# Relay_IO.net
KiCad netlist of a schematic drawn in Altium Designer
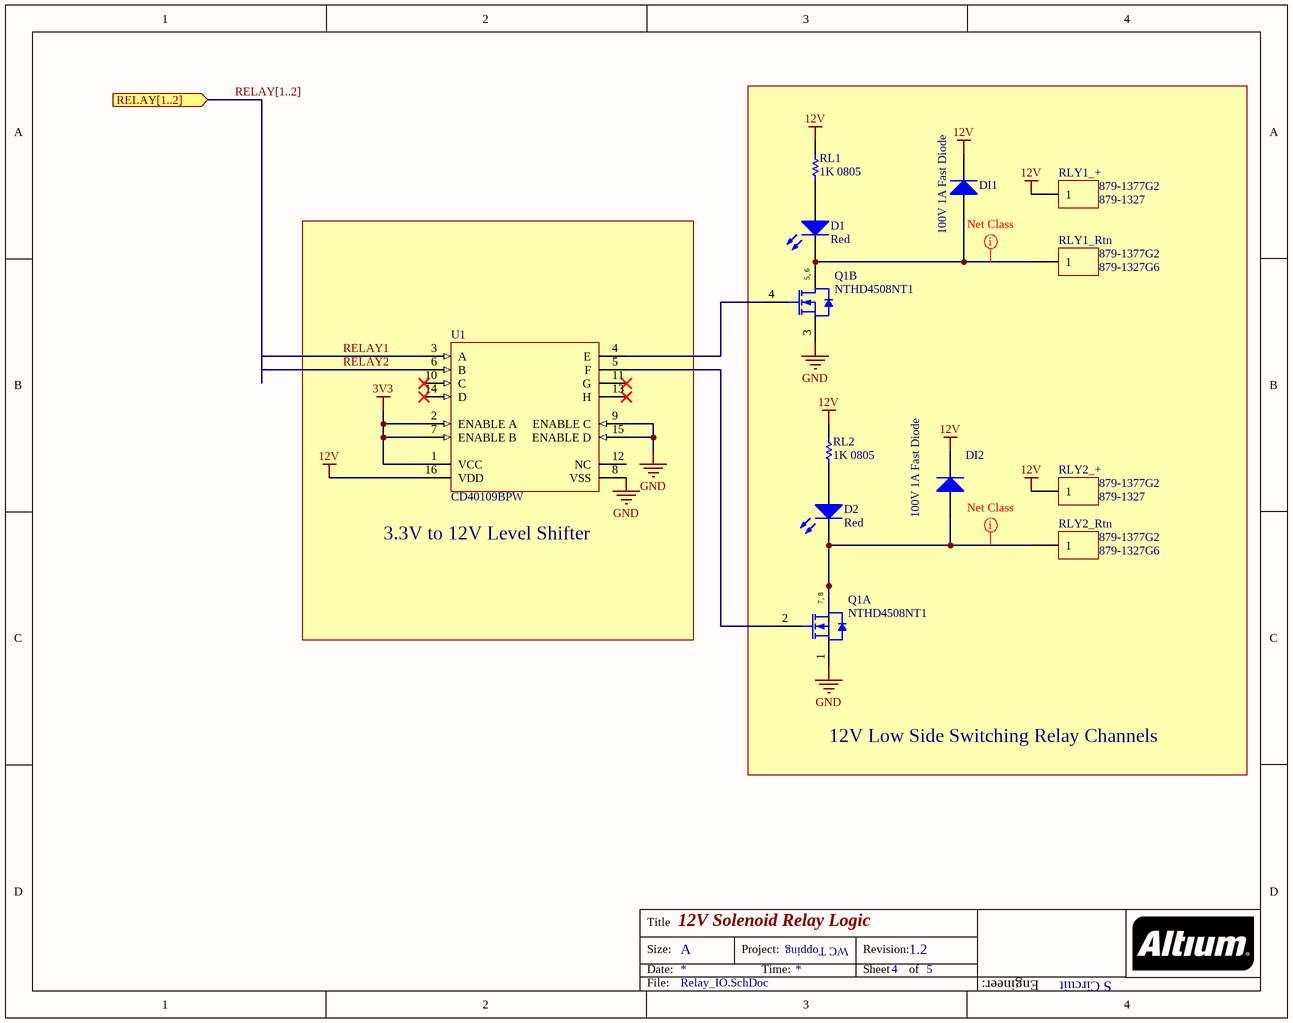
[diagram p0: Relay_IO.SchDoc]

(export (version "E")
  (design (tool "Eeschema 10.0.6"))
  (components
    (comp (ref "D1")
      (value "LED Red")
      (footprint "0603_A")
      (description "SMD mono-color Chip LED, WL-SMCW, Red")
      (fields
        (field (name "COLOR") "Red")
        (field (name "MANUFACTURER") "Wurth Electronics Inc")
        (field (name "MANUFACTURER PART NUMBER") "150060RS75000")
      )
      (libsource (lib "WCT") (part "LED_Red0603"))
    )
    (comp (ref "D2")
      (value "LED Red")
      (footprint "0603_A")
      (description "SMD mono-color Chip LED, WL-SMCW, Red")
      (fields
        (field (name "COLOR") "Red")
        (field (name "MANUFACTURER") "Wurth Electronics Inc")
        (field (name "MANUFACTURER PART NUMBER") "150060RS75000")
      )
      (libsource (lib "WCT") (part "LED_Red0603"))
    )
    (comp (ref "DI1")
      (value "100V 1A Fast Diode")
      (footprint "DO-35")
      (description "High Conductance Fast Diode")
      (fields
        (field (name "MANUFACTURER") "ON Semiconductor")
        (field (name "MANUFACTURER PART NUMBER") "MUR110RLG")
      )
      (libsource (lib "WCT") (part "Diode 1N4148"))
    )
    (comp (ref "DI2")
      (value "100V 1A Fast Diode")
      (footprint "DO-35")
      (description "High Conductance Fast Diode")
      (fields
        (field (name "MANUFACTURER") "ON Semiconductor")
        (field (name "MANUFACTURER PART NUMBER") "MUR110RLG")
      )
      (libsource (lib "WCT") (part "Diode 1N4148"))
    )
    (comp (ref "Q1")
      (value "NTHD4508NT1")
      (footprint "ONSC-CHIPFET-8-1206A-03_S2_V")
      (description "Power MOSFET, 20 V, 4.1 A, Dual N-Channel, 8-Pin CHIPFET, Tape and Reel")
      (fields
        (field (name "MANUFACTURER") "On Semiconductor")
        (field (name "MANUFACTURER PART NUMBER") "NTHD4508NT1G")
      )
      (libsource (lib "WCT") (part "NTHD4508NT1"))
    )
    (comp (ref "RL1")
      (value "1K 0805")
      (footprint "0805_L")
      (fields
        (field (name "MANUFACTURER") "Panasonic Electronic Components")
        (field (name "MANUFACTURER PART NUMBER") "ERJ-6GEYJ102V")
        (field (name "TOLERANCE") "±5%")
      )
      (libsource (lib "ICEdigikey") (part "Res1K_0805"))
    )
    (comp (ref "RL2")
      (value "1K 0805")
      (footprint "0805_L")
      (fields
        (field (name "MANUFACTURER") "Panasonic Electronic Components")
        (field (name "MANUFACTURER PART NUMBER") "ERJ-6GEYJ102V")
        (field (name "TOLERANCE") "±5%")
      )
      (libsource (lib "ICEdigikey") (part "Res1K_0805"))
    )
    (comp (ref "RLY1_+")
      (value "Anderson-1Pin RED_PCB_RHT")
      (footprint "Anderson_Red_RHT_BOT")
      (description "1 pin Anderson")
      (fields
        (field (name "MANUFACTURER") "Anderson Power Products (APP)")
        (field (name "MANUFACTURER PART NUMBER") "1377G1, 1377G2, 1327-BK,137G6-BK")
        (field (name "SUPPLIER PART NUMBER 1") "879-1377G2")
        (field (name "SUPPLIER PART NUMBER 2") "879-1327")
      )
      (libsource (lib "WCT") (part "Anderson-1Pin RED_PCB_RHT"))
    )
    (comp (ref "RLY1_Rtn")
      (value "Anderson-1Pin BLK_PCB_RHT")
      (footprint "Anderson_BLK_RHT_BOT")
      (description "1 pin Anderson")
      (fields
        (field (name "MANUFACTURER") "Anderson Power Products (APP)")
        (field (name "MANUFACTURER PART NUMBER") "1377G1, 1377G2, 1327-BK,137G6-BK")
        (field (name "SUPPLIER PART NUMBER 1") "879-1377G2")
        (field (name "SUPPLIER PART NUMBER 2") "879-1327G6")
      )
      (libsource (lib "WCT") (part "Anderson-1Pin BLK_PCB_RHT"))
    )
    (comp (ref "RLY2_+")
      (value "Anderson-1Pin RED_PCB_RHT")
      (footprint "Anderson_Red_RHT_BOT")
      (description "1 pin Anderson")
      (fields
        (field (name "MANUFACTURER") "Anderson Power Products (APP)")
        (field (name "MANUFACTURER PART NUMBER") "1377G1, 1377G2, 1327-BK,137G6-BK")
        (field (name "SUPPLIER PART NUMBER 1") "879-1377G2")
        (field (name "SUPPLIER PART NUMBER 2") "879-1327")
      )
      (libsource (lib "WCT") (part "Anderson-1Pin RED_PCB_RHT"))
    )
    (comp (ref "RLY2_Rtn")
      (value "Anderson-1Pin BLK_PCB_RHT")
      (footprint "Anderson_BLK_RHT_BOT")
      (description "1 pin Anderson")
      (fields
        (field (name "MANUFACTURER") "Anderson Power Products (APP)")
        (field (name "MANUFACTURER PART NUMBER") "1377G1, 1377G2, 1327-BK,137G6-BK")
        (field (name "SUPPLIER PART NUMBER 1") "879-1377G2")
        (field (name "SUPPLIER PART NUMBER 2") "879-1327G6")
      )
      (libsource (lib "WCT") (part "Anderson-1Pin BLK_PCB_RHT"))
    )
    (comp (ref "U1")
      (value "CD40109BPW")
      (footprint "PW0016A_M")
      (fields (field (name "MANUFACTURER") "Texas Instruments"))
      (libsource (lib "Altium Content Vault") (part "TI-CD40109B-16"))
    )
  )
  (nets
    (net (code "1") (name "/RELAY1") (class "Default")
      (node (ref "U1") (pin "3") (pinfunction "A_3") (pintype "input"))
    )
    (net (code "2") (name "/RELAY2") (class "Default")
      (node (ref "U1") (pin "6") (pinfunction "B_6") (pintype "input"))
    )
    (net (code "4") (name "3V3") (class "Default")
      (node (ref "U1") (pin "1") (pinfunction "VCC_1") (pintype "power_in"))
      (node (ref "U1") (pin "2") (pinfunction "ENABLE_A_2") (pintype "input"))
      (node (ref "U1") (pin "7") (pinfunction "ENABLE_B_7") (pintype "input"))
    )
    (net (code "5") (name "12V") (class "Default")
      (node (ref "DI1") (pin "2") (pinfunction "K_2") (pintype "passive"))
      (node (ref "DI2") (pin "2") (pinfunction "K_2") (pintype "passive"))
      (node (ref "RL1") (pin "2") (pinfunction "2_2") (pintype "passive"))
      (node (ref "RL2") (pin "2") (pinfunction "2_2") (pintype "passive"))
      (node (ref "RLY1_+") (pin "1") (pinfunction "1_1") (pintype "passive"))
      (node (ref "RLY2_+") (pin "1") (pinfunction "1_1") (pintype "passive"))
      (node (ref "U1") (pin "16") (pinfunction "VDD_16") (pintype "power_in"))
    )
    (net (code "6") (name "GND") (class "Default")
      (node (ref "Q1") (pin "1") (pinfunction "S1_1") (pintype "passive"))
      (node (ref "Q1") (pin "3") (pinfunction "S2_3") (pintype "passive"))
      (node (ref "U1") (pin "15") (pinfunction "ENABLE_D_15") (pintype "input"))
      (node (ref "U1") (pin "8") (pinfunction "VSS_8") (pintype "power_in"))
      (node (ref "U1") (pin "9") (pinfunction "ENABLE_C_9") (pintype "input"))
    )
    (net (code "7") (name "Net-(D1-A)") (class "Default")
      (node (ref "D1") (pin "2") (pinfunction "A_2") (pintype "passive"))
      (node (ref "RL1") (pin "1") (pinfunction "1_1") (pintype "passive"))
    )
    (net (code "8") (name "Net-(D1-K)") (class "Default")
      (node (ref "D1") (pin "1") (pinfunction "K_1") (pintype "passive"))
      (node (ref "DI1") (pin "1") (pinfunction "A_1") (pintype "passive"))
      (node (ref "Q1") (pin "5") (pinfunction "D2_5") (pintype "passive"))
      (node (ref "Q1") (pin "6") (pinfunction "D2_6") (pintype "passive"))
      (node (ref "RLY1_Rtn") (pin "1") (pinfunction "1_1") (pintype "passive"))
    )
    (net (code "9") (name "Net-(D2-A)") (class "Default")
      (node (ref "D2") (pin "2") (pinfunction "A_2") (pintype "passive"))
      (node (ref "RL2") (pin "1") (pinfunction "1_1") (pintype "passive"))
    )
    (net (code "10") (name "Net-(D2-K)") (class "Default")
      (node (ref "D2") (pin "1") (pinfunction "K_1") (pintype "passive"))
      (node (ref "DI2") (pin "1") (pinfunction "A_1") (pintype "passive"))
      (node (ref "Q1") (pin "7") (pinfunction "D1_7") (pintype "passive"))
      (node (ref "Q1") (pin "8") (pinfunction "D1_8") (pintype "passive"))
      (node (ref "RLY2_Rtn") (pin "1") (pinfunction "1_1") (pintype "passive"))
    )
    (net (code "11") (name "Net-(Q1A-G1)") (class "Default")
      (node (ref "Q1") (pin "2") (pinfunction "G1_2") (pintype "passive"))
      (node (ref "U1") (pin "5") (pinfunction "F_5") (pintype "tri_state"))
    )
    (net (code "12") (name "Net-(Q1B-G2)") (class "Default")
      (node (ref "Q1") (pin "4") (pinfunction "G2_4") (pintype "passive"))
      (node (ref "U1") (pin "4") (pinfunction "E_4") (pintype "tri_state"))
    )
    (net (code "13") (name "unconnected-(U1-C-Pad10)") (class "Default")
      (node (ref "U1") (pin "10") (pinfunction "C_10") (pintype "input+no_connect"))
    )
    (net (code "14") (name "unconnected-(U1-D-Pad14)") (class "Default")
      (node (ref "U1") (pin "14") (pinfunction "D_14") (pintype "input+no_connect"))
    )
    (net (code "15") (name "unconnected-(U1-G-Pad11)") (class "Default")
      (node (ref "U1") (pin "11") (pinfunction "G_11") (pintype "tri_state+no_connect"))
    )
    (net (code "16") (name "unconnected-(U1-H-Pad13)") (class "Default")
      (node (ref "U1") (pin "13") (pinfunction "H_13") (pintype "tri_state+no_connect"))
    )
    (net (code "17") (name "unconnected-(U1-NC-Pad12)") (class "Default")
      (node (ref "U1") (pin "12") (pinfunction "NC_12") (pintype "passive"))
    )
  )
)
